# DRLTransistor.net
KiCad netlist of a schematic drawn in Altium Designer
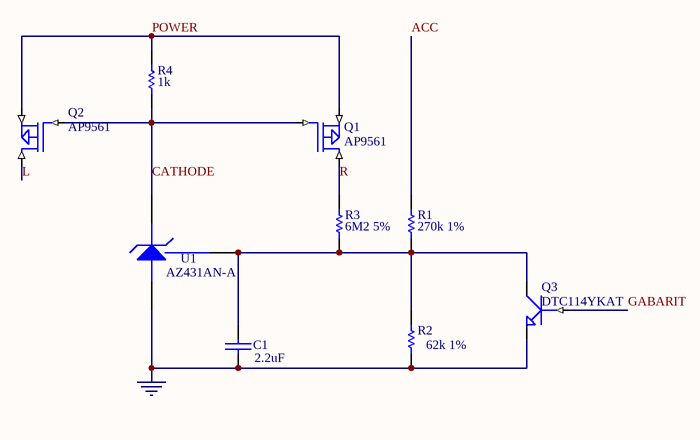
[diagram p0: DRLTransistor.SchDoc]

(export (version "E")
  (design (tool "Eeschema 10.0.6"))
  (components
    (comp (ref "C1")
      (value "2.2uF")
      (footprint "0805")
      (description "Capacitor")
      (libsource (lib "*") (part "CAP"))
    )
    (comp (ref "Q1") (value "AP9561") (footprint "D-Pack") (libsource (lib "*") (part "MOSFET P")))
    (comp (ref "Q2") (value "AP9561") (footprint "D-Pack") (libsource (lib "*") (part "MOSFET P")))
    (comp (ref "Q3")
      (value "DTC114YKAT")
      (footprint "SOT-23")
      (description "NPN Transistor")
      (libsource (lib "Miscellaneous Devices") (part "NPN1"))
    )
    (comp (ref "R1")
      (value "270k 1%")
      (footprint "0805")
      (description "Resistor")
      (fields
        (field (name "MANUFACTURER") "Generic Components")
        (field (name "PUBLISHER") "Altium Hobart Technology Centre")
      )
      (libsource (lib "Miscellaneous Devices") (part "Res1"))
    )
    (comp (ref "R2")
      (value "62k 1%")
      (footprint "0805")
      (description "Resistor")
      (fields
        (field (name "MANUFACTURER") "Generic Components")
        (field (name "PUBLISHER") "Altium Hobart Technology Centre")
      )
      (libsource (lib "Miscellaneous Devices") (part "Res1"))
    )
    (comp (ref "R3")
      (value "6M2 5%")
      (footprint "0805")
      (description "Resistor")
      (fields
        (field (name "MANUFACTURER") "Generic Components")
        (field (name "PUBLISHER") "Altium Hobart Technology Centre")
      )
      (libsource (lib "Miscellaneous Devices") (part "Res1"))
    )
    (comp (ref "R4")
      (value "1k")
      (footprint "1206")
      (description "Resistor")
      (fields
        (field (name "MANUFACTURER") "Generic Components")
        (field (name "PUBLISHER") "Altium Hobart Technology Centre")
      )
      (libsource (lib "Miscellaneous Devices") (part "Res1"))
    )
    (comp (ref "U1") (value "AZ431AN-A") (footprint "SOT-23") (libsource (lib "Devices") (part "TL431")))
  )
  (nets
    (net (code "1") (name "/ACC") (class "Default")
      (node (ref "R1") (pin "1") (pinfunction "1_1") (pintype "passive"))
    )
    (net (code "2") (name "/CATHODE") (class "Default")
      (node (ref "Q1") (pin "1") (pinfunction "GATE_1") (pintype "input"))
      (node (ref "Q2") (pin "1") (pinfunction "GATE_1") (pintype "input"))
      (node (ref "R4") (pin "2") (pinfunction "2_2") (pintype "passive"))
      (node (ref "U1") (pin "3") (pinfunction "K_3") (pintype "passive"))
    )
    (net (code "3") (name "/GABARIT") (class "Default")
      (node (ref "Q3") (pin "1") (pinfunction "B_1") (pintype "input"))
    )
    (net (code "4") (name "/L") (class "Default")
      (node (ref "Q2") (pin "2") (pinfunction "DRAIN_2") (pintype "input"))
    )
    (net (code "5") (name "/POWER") (class "Default")
      (node (ref "Q1") (pin "3") (pinfunction "SOURCE_3") (pintype "input"))
      (node (ref "Q2") (pin "3") (pinfunction "SOURCE_3") (pintype "input"))
      (node (ref "R4") (pin "1") (pinfunction "1_1") (pintype "passive"))
    )
    (net (code "6") (name "/R") (class "Default")
      (node (ref "Q1") (pin "2") (pinfunction "DRAIN_2") (pintype "input"))
      (node (ref "R3") (pin "1") (pinfunction "1_1") (pintype "passive"))
    )
    (net (code "7") (name "Net-(Q3-C)") (class "Default")
      (node (ref "C1") (pin "1") (pinfunction "1_1") (pintype "passive"))
      (node (ref "Q3") (pin "2") (pinfunction "C_2") (pintype "passive"))
      (node (ref "R1") (pin "2") (pinfunction "2_2") (pintype "passive"))
      (node (ref "R2") (pin "1") (pinfunction "1_1") (pintype "passive"))
      (node (ref "R3") (pin "2") (pinfunction "2_2") (pintype "passive"))
      (node (ref "U1") (pin "1") (pinfunction "REF_1") (pintype "passive"))
    )
    (net (code "8") (name "PGND") (class "Default")
      (node (ref "C1") (pin "2") (pinfunction "2_2") (pintype "passive"))
      (node (ref "Q3") (pin "3") (pinfunction "E_3") (pintype "passive"))
      (node (ref "R2") (pin "2") (pinfunction "2_2") (pintype "passive"))
      (node (ref "U1") (pin "2") (pinfunction "A_2") (pintype "passive"))
    )
  )
)
